# D_INPUT.net
KiCad netlist of a schematic drawn in Altium Designer
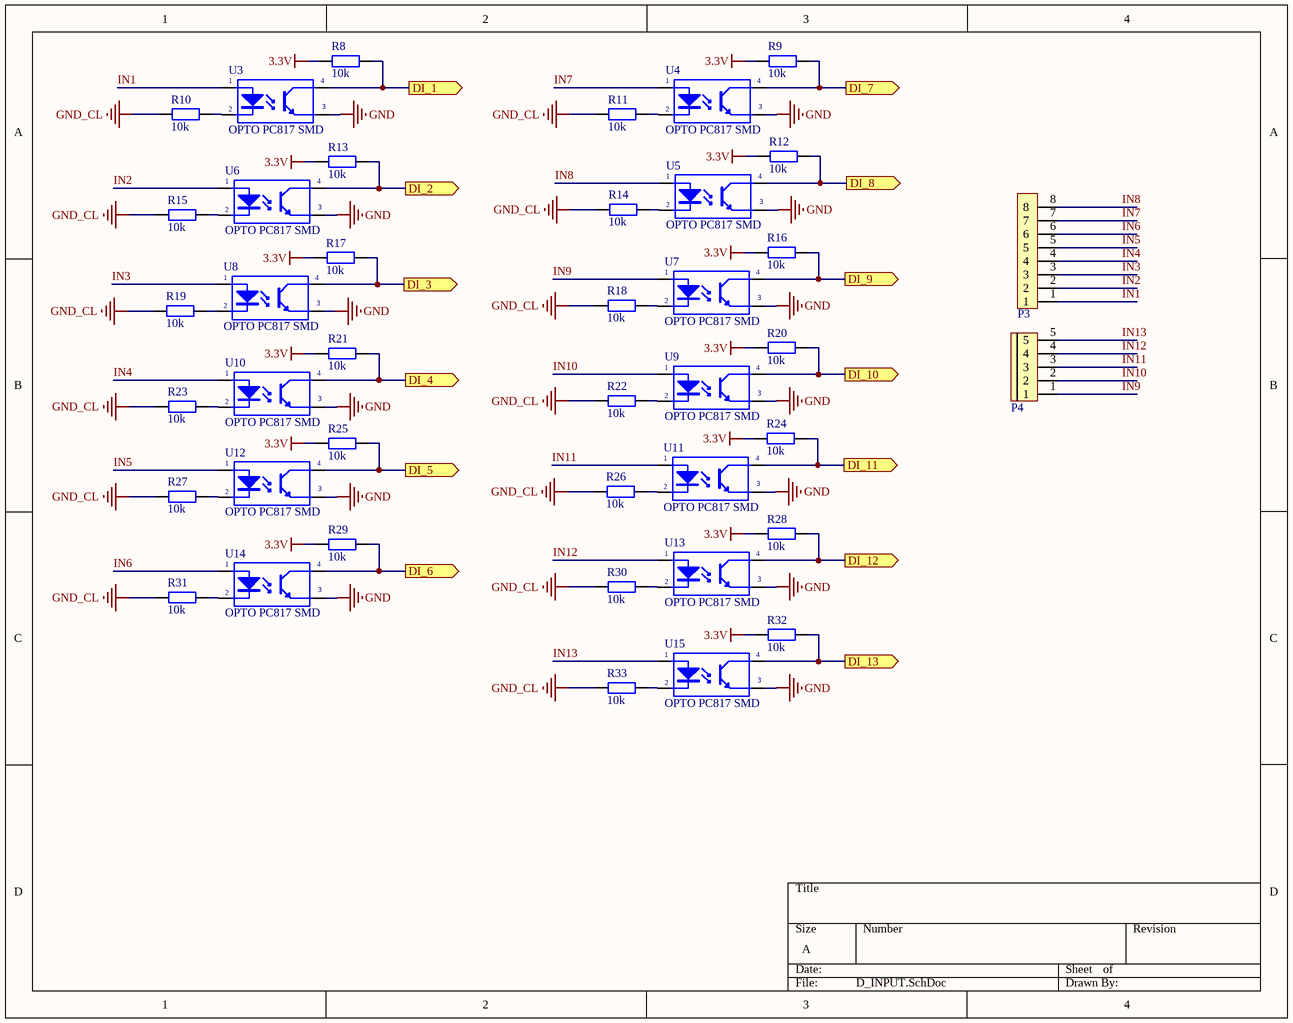
[diagram p0: D_INPUT.SchDoc]

(export (version "E")
  (design (tool "Eeschema 10.0.6"))
  (components
    (comp (ref "P3")
      (value "CON 8 EDG5.08")
      (footprint "CON 8 8EDG5.08")
      (description "Cắm")
      (libsource (lib "Altium_Lib_by_KhueNguyenCreator") (part "CON 8 EDG5.08"))
    )
    (comp (ref "P4")
      (value "CON 5 EDG5.08")
      (footprint "CON 5 5EDG5.08")
      (description "Cắm")
      (libsource (lib "Altium_Lib_by_KhueNguyenCreator") (part "CON 5 EDG5.08"))
    )
    (comp (ref "R8")
      (value "10k")
      (footprint "tro smd 0805")
      (description "Dán")
      (libsource (lib "Altium_Lib_by_KhueNguyenCreator") (part "Tro 0805 5% 10k"))
    )
    (comp (ref "R9")
      (value "10k")
      (footprint "tro smd 0805")
      (description "Dán")
      (libsource (lib "Altium_Lib_by_KhueNguyenCreator") (part "Tro 0805 5% 10k"))
    )
    (comp (ref "R10")
      (value "10k")
      (footprint "tro smd 0805")
      (description "Dán")
      (libsource (lib "Altium_Lib_by_KhueNguyenCreator") (part "Tro 0805 5% 10k"))
    )
    (comp (ref "R11")
      (value "10k")
      (footprint "tro smd 0805")
      (description "Dán")
      (libsource (lib "Altium_Lib_by_KhueNguyenCreator") (part "Tro 0805 5% 10k"))
    )
    (comp (ref "R12")
      (value "10k")
      (footprint "tro smd 0805")
      (description "Dán")
      (libsource (lib "Altium_Lib_by_KhueNguyenCreator") (part "Tro 0805 5% 10k"))
    )
    (comp (ref "R13")
      (value "10k")
      (footprint "tro smd 0805")
      (description "Dán")
      (libsource (lib "Altium_Lib_by_KhueNguyenCreator") (part "Tro 0805 5% 10k"))
    )
    (comp (ref "R14")
      (value "10k")
      (footprint "tro smd 0805")
      (description "Dán")
      (libsource (lib "Altium_Lib_by_KhueNguyenCreator") (part "Tro 0805 5% 10k"))
    )
    (comp (ref "R15")
      (value "10k")
      (footprint "tro smd 0805")
      (description "Dán")
      (libsource (lib "Altium_Lib_by_KhueNguyenCreator") (part "Tro 0805 5% 10k"))
    )
    (comp (ref "R16")
      (value "10k")
      (footprint "tro smd 0805")
      (description "Dán")
      (libsource (lib "Altium_Lib_by_KhueNguyenCreator") (part "Tro 0805 5% 10k"))
    )
    (comp (ref "R17")
      (value "10k")
      (footprint "tro smd 0805")
      (description "Dán")
      (libsource (lib "Altium_Lib_by_KhueNguyenCreator") (part "Tro 0805 5% 10k"))
    )
    (comp (ref "R18")
      (value "10k")
      (footprint "tro smd 0805")
      (description "Dán")
      (libsource (lib "Altium_Lib_by_KhueNguyenCreator") (part "Tro 0805 5% 10k"))
    )
    (comp (ref "R19")
      (value "10k")
      (footprint "tro smd 0805")
      (description "Dán")
      (libsource (lib "Altium_Lib_by_KhueNguyenCreator") (part "Tro 0805 5% 10k"))
    )
    (comp (ref "R20")
      (value "10k")
      (footprint "tro smd 0805")
      (description "Dán")
      (libsource (lib "Altium_Lib_by_KhueNguyenCreator") (part "Tro 0805 5% 10k"))
    )
    (comp (ref "R21")
      (value "10k")
      (footprint "tro smd 0805")
      (description "Dán")
      (libsource (lib "Altium_Lib_by_KhueNguyenCreator") (part "Tro 0805 5% 10k"))
    )
    (comp (ref "R22")
      (value "10k")
      (footprint "tro smd 0805")
      (description "Dán")
      (libsource (lib "Altium_Lib_by_KhueNguyenCreator") (part "Tro 0805 5% 10k"))
    )
    (comp (ref "R23")
      (value "10k")
      (footprint "tro smd 0805")
      (description "Dán")
      (libsource (lib "Altium_Lib_by_KhueNguyenCreator") (part "Tro 0805 5% 10k"))
    )
    (comp (ref "R24")
      (value "10k")
      (footprint "tro smd 0805")
      (description "Dán")
      (libsource (lib "Altium_Lib_by_KhueNguyenCreator") (part "Tro 0805 5% 10k"))
    )
    (comp (ref "R25")
      (value "10k")
      (footprint "tro smd 0805")
      (description "Dán")
      (libsource (lib "Altium_Lib_by_KhueNguyenCreator") (part "Tro 0805 5% 10k"))
    )
    (comp (ref "R26")
      (value "10k")
      (footprint "tro smd 0805")
      (description "Dán")
      (libsource (lib "Altium_Lib_by_KhueNguyenCreator") (part "Tro 0805 5% 10k"))
    )
    (comp (ref "R27")
      (value "10k")
      (footprint "tro smd 0805")
      (description "Dán")
      (libsource (lib "Altium_Lib_by_KhueNguyenCreator") (part "Tro 0805 5% 10k"))
    )
    (comp (ref "R28")
      (value "10k")
      (footprint "tro smd 0805")
      (description "Dán")
      (libsource (lib "Altium_Lib_by_KhueNguyenCreator") (part "Tro 0805 5% 10k"))
    )
    (comp (ref "R29")
      (value "10k")
      (footprint "tro smd 0805")
      (description "Dán")
      (libsource (lib "Altium_Lib_by_KhueNguyenCreator") (part "Tro 0805 5% 10k"))
    )
    (comp (ref "R30")
      (value "10k")
      (footprint "tro smd 0805")
      (description "Dán")
      (libsource (lib "Altium_Lib_by_KhueNguyenCreator") (part "Tro 0805 5% 10k"))
    )
    (comp (ref "R31")
      (value "10k")
      (footprint "tro smd 0805")
      (description "Dán")
      (libsource (lib "Altium_Lib_by_KhueNguyenCreator") (part "Tro 0805 5% 10k"))
    )
    (comp (ref "R32")
      (value "10k")
      (footprint "tro smd 0805")
      (description "Dán")
      (libsource (lib "Altium_Lib_by_KhueNguyenCreator") (part "Tro 0805 5% 10k"))
    )
    (comp (ref "R33")
      (value "10k")
      (footprint "tro smd 0805")
      (description "Dán")
      (libsource (lib "Altium_Lib_by_KhueNguyenCreator") (part "Tro 0805 5% 10k"))
    )
    (comp (ref "U3")
      (value "OPTO PC817 SMD")
      (footprint "SOP4")
      (description "Single Opto")
      (libsource (lib "Altium_Lib_by_KhueNguyenCreator") (part "OPTO PC817 SMD"))
    )
    (comp (ref "U4")
      (value "OPTO PC817 SMD")
      (footprint "SOP4")
      (description "Single Opto")
      (libsource (lib "Altium_Lib_by_KhueNguyenCreator") (part "OPTO PC817 SMD"))
    )
    (comp (ref "U5")
      (value "OPTO PC817 SMD")
      (footprint "SOP4")
      (description "Single Opto")
      (libsource (lib "Altium_Lib_by_KhueNguyenCreator") (part "OPTO PC817 SMD"))
    )
    (comp (ref "U6")
      (value "OPTO PC817 SMD")
      (footprint "SOP4")
      (description "Single Opto")
      (libsource (lib "Altium_Lib_by_KhueNguyenCreator") (part "OPTO PC817 SMD"))
    )
    (comp (ref "U7")
      (value "OPTO PC817 SMD")
      (footprint "SOP4")
      (description "Single Opto")
      (libsource (lib "Altium_Lib_by_KhueNguyenCreator") (part "OPTO PC817 SMD"))
    )
    (comp (ref "U8")
      (value "OPTO PC817 SMD")
      (footprint "SOP4")
      (description "Single Opto")
      (libsource (lib "Altium_Lib_by_KhueNguyenCreator") (part "OPTO PC817 SMD"))
    )
    (comp (ref "U9")
      (value "OPTO PC817 SMD")
      (footprint "SOP4")
      (description "Single Opto")
      (libsource (lib "Altium_Lib_by_KhueNguyenCreator") (part "OPTO PC817 SMD"))
    )
    (comp (ref "U10")
      (value "OPTO PC817 SMD")
      (footprint "SOP4")
      (description "Single Opto")
      (libsource (lib "Altium_Lib_by_KhueNguyenCreator") (part "OPTO PC817 SMD"))
    )
    (comp (ref "U11")
      (value "OPTO PC817 SMD")
      (footprint "SOP4")
      (description "Single Opto")
      (libsource (lib "Altium_Lib_by_KhueNguyenCreator") (part "OPTO PC817 SMD"))
    )
    (comp (ref "U12")
      (value "OPTO PC817 SMD")
      (footprint "SOP4")
      (description "Single Opto")
      (libsource (lib "Altium_Lib_by_KhueNguyenCreator") (part "OPTO PC817 SMD"))
    )
    (comp (ref "U13")
      (value "OPTO PC817 SMD")
      (footprint "SOP4")
      (description "Single Opto")
      (libsource (lib "Altium_Lib_by_KhueNguyenCreator") (part "OPTO PC817 SMD"))
    )
    (comp (ref "U14")
      (value "OPTO PC817 SMD")
      (footprint "SOP4")
      (description "Single Opto")
      (libsource (lib "Altium_Lib_by_KhueNguyenCreator") (part "OPTO PC817 SMD"))
    )
    (comp (ref "U15")
      (value "OPTO PC817 SMD")
      (footprint "SOP4")
      (description "Single Opto")
      (libsource (lib "Altium_Lib_by_KhueNguyenCreator") (part "OPTO PC817 SMD"))
    )
  )
  (nets
    (net (code "1") (name "/DI_1") (class "Default")
      (node (ref "R8") (pin "1") (pinfunction "1_1") (pintype "passive"))
      (node (ref "U3") (pin "4") (pinfunction "C_4") (pintype "passive"))
    )
    (net (code "2") (name "/DI_2") (class "Default")
      (node (ref "R13") (pin "1") (pinfunction "1_1") (pintype "passive"))
      (node (ref "U6") (pin "4") (pinfunction "C_4") (pintype "passive"))
    )
    (net (code "3") (name "/DI_3") (class "Default")
      (node (ref "R17") (pin "1") (pinfunction "1_1") (pintype "passive"))
      (node (ref "U8") (pin "4") (pinfunction "C_4") (pintype "passive"))
    )
    (net (code "4") (name "/DI_4") (class "Default")
      (node (ref "R21") (pin "1") (pinfunction "1_1") (pintype "passive"))
      (node (ref "U10") (pin "4") (pinfunction "C_4") (pintype "passive"))
    )
    (net (code "5") (name "/DI_5") (class "Default")
      (node (ref "R25") (pin "1") (pinfunction "1_1") (pintype "passive"))
      (node (ref "U12") (pin "4") (pinfunction "C_4") (pintype "passive"))
    )
    (net (code "6") (name "/DI_6") (class "Default")
      (node (ref "R29") (pin "1") (pinfunction "1_1") (pintype "passive"))
      (node (ref "U14") (pin "4") (pinfunction "C_4") (pintype "passive"))
    )
    (net (code "7") (name "/DI_7") (class "Default")
      (node (ref "R9") (pin "1") (pinfunction "1_1") (pintype "passive"))
      (node (ref "U4") (pin "4") (pinfunction "C_4") (pintype "passive"))
    )
    (net (code "8") (name "/DI_8") (class "Default")
      (node (ref "R12") (pin "1") (pinfunction "1_1") (pintype "passive"))
      (node (ref "U5") (pin "4") (pinfunction "C_4") (pintype "passive"))
    )
    (net (code "9") (name "/DI_9") (class "Default")
      (node (ref "R16") (pin "1") (pinfunction "1_1") (pintype "passive"))
      (node (ref "U7") (pin "4") (pinfunction "C_4") (pintype "passive"))
    )
    (net (code "10") (name "/DI_10") (class "Default")
      (node (ref "R20") (pin "1") (pinfunction "1_1") (pintype "passive"))
      (node (ref "U9") (pin "4") (pinfunction "C_4") (pintype "passive"))
    )
    (net (code "11") (name "/DI_11") (class "Default")
      (node (ref "R24") (pin "1") (pinfunction "1_1") (pintype "passive"))
      (node (ref "U11") (pin "4") (pinfunction "C_4") (pintype "passive"))
    )
    (net (code "12") (name "/DI_12") (class "Default")
      (node (ref "R28") (pin "1") (pinfunction "1_1") (pintype "passive"))
      (node (ref "U13") (pin "4") (pinfunction "C_4") (pintype "passive"))
    )
    (net (code "13") (name "/DI_13") (class "Default")
      (node (ref "R32") (pin "1") (pinfunction "1_1") (pintype "passive"))
      (node (ref "U15") (pin "4") (pinfunction "C_4") (pintype "passive"))
    )
    (net (code "14") (name "/IN1") (class "Default")
      (node (ref "P3") (pin "1") (pinfunction "1_1") (pintype "passive"))
      (node (ref "U3") (pin "1") (pinfunction "A_1") (pintype "passive"))
    )
    (net (code "15") (name "/IN2") (class "Default")
      (node (ref "P3") (pin "2") (pinfunction "2_2") (pintype "passive"))
      (node (ref "U6") (pin "1") (pinfunction "A_1") (pintype "passive"))
    )
    (net (code "16") (name "/IN3") (class "Default")
      (node (ref "P3") (pin "3") (pinfunction "3_3") (pintype "passive"))
      (node (ref "U8") (pin "1") (pinfunction "A_1") (pintype "passive"))
    )
    (net (code "17") (name "/IN4") (class "Default")
      (node (ref "P3") (pin "4") (pinfunction "4_4") (pintype "passive"))
      (node (ref "U10") (pin "1") (pinfunction "A_1") (pintype "passive"))
    )
    (net (code "18") (name "/IN5") (class "Default")
      (node (ref "P3") (pin "5") (pinfunction "5_5") (pintype "passive"))
      (node (ref "U12") (pin "1") (pinfunction "A_1") (pintype "passive"))
    )
    (net (code "19") (name "/IN6") (class "Default")
      (node (ref "P3") (pin "6") (pinfunction "6_6") (pintype "passive"))
      (node (ref "U14") (pin "1") (pinfunction "A_1") (pintype "passive"))
    )
    (net (code "20") (name "/IN7") (class "Default")
      (node (ref "P3") (pin "7") (pinfunction "7_7") (pintype "passive"))
      (node (ref "U4") (pin "1") (pinfunction "A_1") (pintype "passive"))
    )
    (net (code "21") (name "/IN8") (class "Default")
      (node (ref "P3") (pin "8") (pinfunction "8_8") (pintype "passive"))
      (node (ref "U5") (pin "1") (pinfunction "A_1") (pintype "passive"))
    )
    (net (code "22") (name "/IN9") (class "Default")
      (node (ref "P4") (pin "1") (pinfunction "1_1") (pintype "passive"))
      (node (ref "U7") (pin "1") (pinfunction "A_1") (pintype "passive"))
    )
    (net (code "23") (name "/IN10") (class "Default")
      (node (ref "P4") (pin "2") (pinfunction "2_2") (pintype "passive"))
      (node (ref "U9") (pin "1") (pinfunction "A_1") (pintype "passive"))
    )
    (net (code "24") (name "/IN11") (class "Default")
      (node (ref "P4") (pin "3") (pinfunction "3_3") (pintype "passive"))
      (node (ref "U11") (pin "1") (pinfunction "A_1") (pintype "passive"))
    )
    (net (code "25") (name "/IN12") (class "Default")
      (node (ref "P4") (pin "4") (pinfunction "4_4") (pintype "passive"))
      (node (ref "U13") (pin "1") (pinfunction "A_1") (pintype "passive"))
    )
    (net (code "26") (name "/IN13") (class "Default")
      (node (ref "P4") (pin "5") (pinfunction "5_5") (pintype "passive"))
      (node (ref "U15") (pin "1") (pinfunction "A_1") (pintype "passive"))
    )
    (net (code "27") (name "3.3V") (class "Default")
      (node (ref "R12") (pin "2") (pinfunction "2_2") (pintype "passive"))
      (node (ref "R13") (pin "2") (pinfunction "2_2") (pintype "passive"))
      (node (ref "R16") (pin "2") (pinfunction "2_2") (pintype "passive"))
      (node (ref "R17") (pin "2") (pinfunction "2_2") (pintype "passive"))
      (node (ref "R20") (pin "2") (pinfunction "2_2") (pintype "passive"))
      (node (ref "R21") (pin "2") (pinfunction "2_2") (pintype "passive"))
      (node (ref "R24") (pin "2") (pinfunction "2_2") (pintype "passive"))
      (node (ref "R25") (pin "2") (pinfunction "2_2") (pintype "passive"))
      (node (ref "R28") (pin "2") (pinfunction "2_2") (pintype "passive"))
      (node (ref "R29") (pin "2") (pinfunction "2_2") (pintype "passive"))
      (node (ref "R32") (pin "2") (pinfunction "2_2") (pintype "passive"))
      (node (ref "R8") (pin "2") (pinfunction "2_2") (pintype "passive"))
      (node (ref "R9") (pin "2") (pinfunction "2_2") (pintype "passive"))
    )
    (net (code "28") (name "GND") (class "Default")
      (node (ref "U10") (pin "3") (pinfunction "E_3") (pintype "passive"))
      (node (ref "U11") (pin "3") (pinfunction "E_3") (pintype "passive"))
      (node (ref "U12") (pin "3") (pinfunction "E_3") (pintype "passive"))
      (node (ref "U13") (pin "3") (pinfunction "E_3") (pintype "passive"))
      (node (ref "U14") (pin "3") (pinfunction "E_3") (pintype "passive"))
      (node (ref "U15") (pin "3") (pinfunction "E_3") (pintype "passive"))
      (node (ref "U3") (pin "3") (pinfunction "E_3") (pintype "passive"))
      (node (ref "U4") (pin "3") (pinfunction "E_3") (pintype "passive"))
      (node (ref "U5") (pin "3") (pinfunction "E_3") (pintype "passive"))
      (node (ref "U6") (pin "3") (pinfunction "E_3") (pintype "passive"))
      (node (ref "U7") (pin "3") (pinfunction "E_3") (pintype "passive"))
      (node (ref "U8") (pin "3") (pinfunction "E_3") (pintype "passive"))
      (node (ref "U9") (pin "3") (pinfunction "E_3") (pintype "passive"))
    )
    (net (code "29") (name "GND_CL") (class "Default")
      (node (ref "R10") (pin "2") (pinfunction "2_2") (pintype "passive"))
      (node (ref "R11") (pin "2") (pinfunction "2_2") (pintype "passive"))
      (node (ref "R14") (pin "2") (pinfunction "2_2") (pintype "passive"))
      (node (ref "R15") (pin "2") (pinfunction "2_2") (pintype "passive"))
      (node (ref "R18") (pin "2") (pinfunction "2_2") (pintype "passive"))
      (node (ref "R19") (pin "2") (pinfunction "2_2") (pintype "passive"))
      (node (ref "R22") (pin "2") (pinfunction "2_2") (pintype "passive"))
      (node (ref "R23") (pin "2") (pinfunction "2_2") (pintype "passive"))
      (node (ref "R26") (pin "2") (pinfunction "2_2") (pintype "passive"))
      (node (ref "R27") (pin "2") (pinfunction "2_2") (pintype "passive"))
      (node (ref "R30") (pin "2") (pinfunction "2_2") (pintype "passive"))
      (node (ref "R31") (pin "2") (pinfunction "2_2") (pintype "passive"))
      (node (ref "R33") (pin "2") (pinfunction "2_2") (pintype "passive"))
    )
    (net (code "30") (name "Net-(U3-K)") (class "Default")
      (node (ref "R10") (pin "1") (pinfunction "1_1") (pintype "passive"))
      (node (ref "U3") (pin "2") (pinfunction "K_2") (pintype "passive"))
    )
    (net (code "31") (name "Net-(U4-K)") (class "Default")
      (node (ref "R11") (pin "1") (pinfunction "1_1") (pintype "passive"))
      (node (ref "U4") (pin "2") (pinfunction "K_2") (pintype "passive"))
    )
    (net (code "32") (name "Net-(U5-K)") (class "Default")
      (node (ref "R14") (pin "1") (pinfunction "1_1") (pintype "passive"))
      (node (ref "U5") (pin "2") (pinfunction "K_2") (pintype "passive"))
    )
    (net (code "33") (name "Net-(U6-K)") (class "Default")
      (node (ref "R15") (pin "1") (pinfunction "1_1") (pintype "passive"))
      (node (ref "U6") (pin "2") (pinfunction "K_2") (pintype "passive"))
    )
    (net (code "34") (name "Net-(U7-K)") (class "Default")
      (node (ref "R18") (pin "1") (pinfunction "1_1") (pintype "passive"))
      (node (ref "U7") (pin "2") (pinfunction "K_2") (pintype "passive"))
    )
    (net (code "35") (name "Net-(U8-K)") (class "Default")
      (node (ref "R19") (pin "1") (pinfunction "1_1") (pintype "passive"))
      (node (ref "U8") (pin "2") (pinfunction "K_2") (pintype "passive"))
    )
    (net (code "36") (name "Net-(U9-K)") (class "Default")
      (node (ref "R22") (pin "1") (pinfunction "1_1") (pintype "passive"))
      (node (ref "U9") (pin "2") (pinfunction "K_2") (pintype "passive"))
    )
    (net (code "37") (name "Net-(U10-K)") (class "Default")
      (node (ref "R23") (pin "1") (pinfunction "1_1") (pintype "passive"))
      (node (ref "U10") (pin "2") (pinfunction "K_2") (pintype "passive"))
    )
    (net (code "38") (name "Net-(U11-K)") (class "Default")
      (node (ref "R26") (pin "1") (pinfunction "1_1") (pintype "passive"))
      (node (ref "U11") (pin "2") (pinfunction "K_2") (pintype "passive"))
    )
    (net (code "39") (name "Net-(U12-K)") (class "Default")
      (node (ref "R27") (pin "1") (pinfunction "1_1") (pintype "passive"))
      (node (ref "U12") (pin "2") (pinfunction "K_2") (pintype "passive"))
    )
    (net (code "40") (name "Net-(U13-K)") (class "Default")
      (node (ref "R30") (pin "1") (pinfunction "1_1") (pintype "passive"))
      (node (ref "U13") (pin "2") (pinfunction "K_2") (pintype "passive"))
    )
    (net (code "41") (name "Net-(U14-K)") (class "Default")
      (node (ref "R31") (pin "1") (pinfunction "1_1") (pintype "passive"))
      (node (ref "U14") (pin "2") (pinfunction "K_2") (pintype "passive"))
    )
    (net (code "42") (name "Net-(U15-K)") (class "Default")
      (node (ref "R33") (pin "1") (pinfunction "1_1") (pintype "passive"))
      (node (ref "U15") (pin "2") (pinfunction "K_2") (pintype "passive"))
    )
  )
)
